# esp-plane-u.net
KiCad netlist of a schematic drawn in Altium Designer
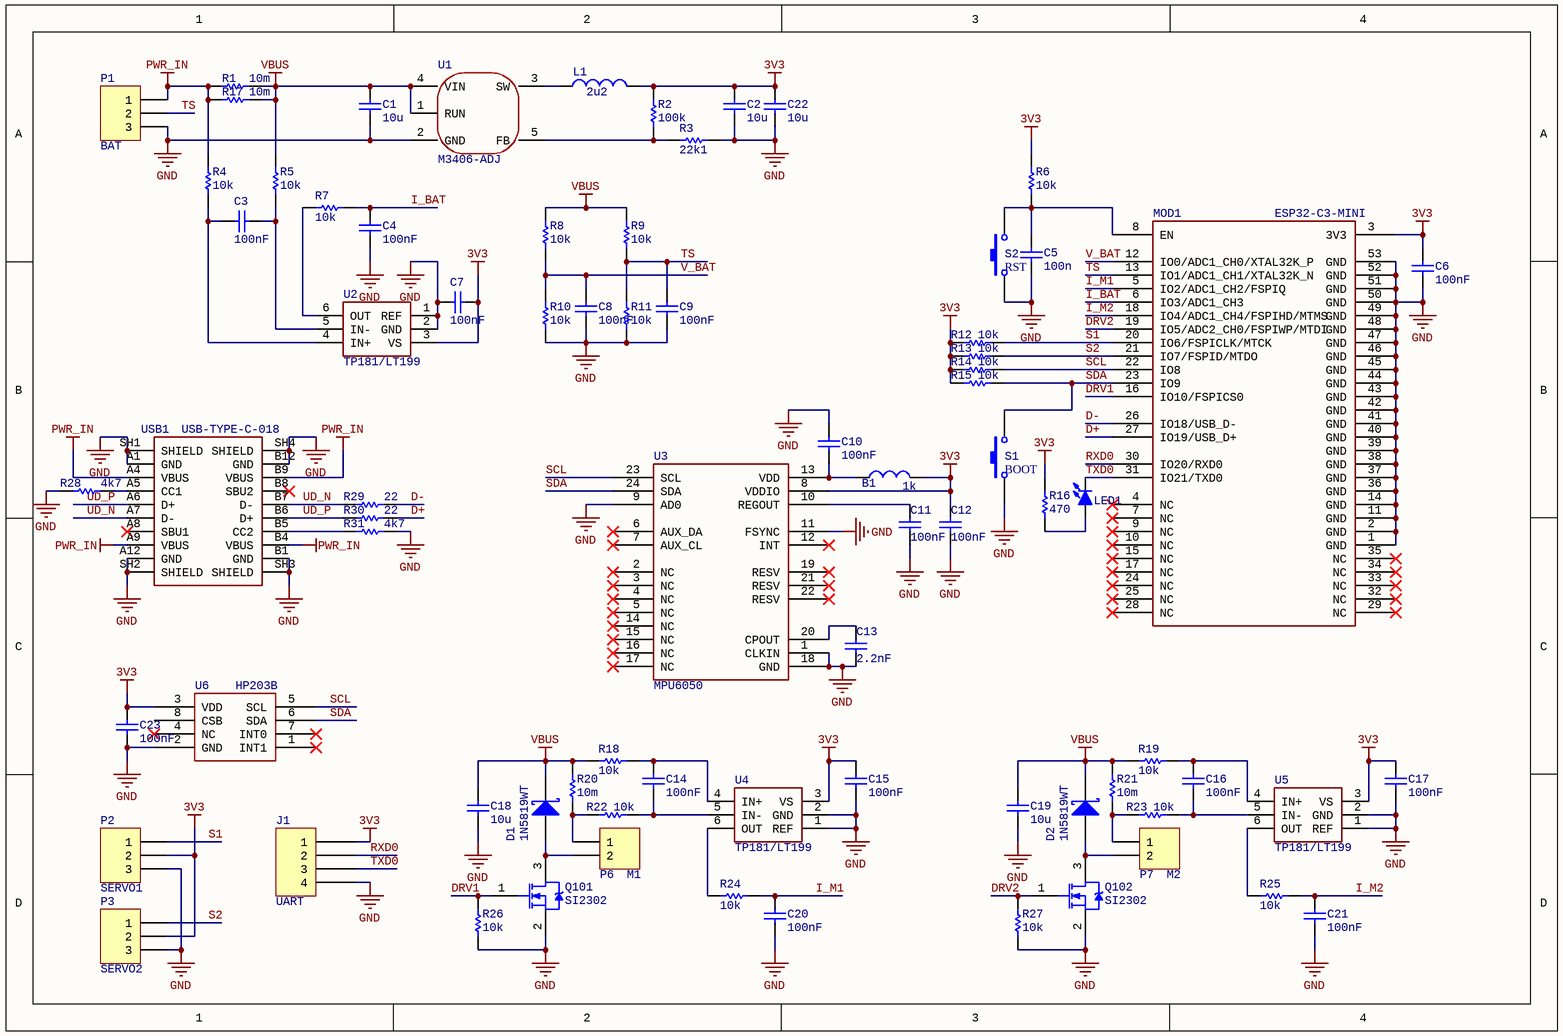
[diagram p0: esp-plane-u.SchDoc]

(export (version "E")
  (design (tool "Eeschema 10.0.6"))
  (components
    (comp (ref "B1")
      (value "1k")
      (footprint "footprints:RESC100X50X35L25N")
      (description "DCR 0.03,2A  0603")
      (fields
        (field (name "MPN") "GZ1005D102CTF")
        (field (name "Comment") "BEAD-470-100MHZ-1A-0603-BLM18PG471SN1")
      )
      (libsource (lib "*") (part "BEAD-470-100MHZ-1A-0603-BLM18PG471SN1"))
    )
    (comp (ref "C1")
      (value "10u")
      (footprint "footprints:CAPC160X80X90L30N")
      (fields (field (name "MPN") "TCC0603X5R106K100CT"))
      (libsource (lib "std_lib") (part "Capacitor"))
    )
    (comp (ref "C2")
      (value "10u")
      (footprint "footprints:CAPC160X80X90L30N")
      (fields (field (name "MPN") "TCC0603X5R106K100CT"))
      (libsource (lib "std_lib") (part "Capacitor"))
    )
    (comp (ref "C3")
      (value "100nF")
      (footprint "footprints:CAPC100X50X55L25N")
      (description "Capacitor")
      (libsource (lib "Miscellaneous Devices") (part "Cap"))
    )
    (comp (ref "C4")
      (value "100nF")
      (footprint "footprints:CAPC100X50X55L25N")
      (description "Capacitor")
      (libsource (lib "Miscellaneous Devices") (part "Cap"))
    )
    (comp (ref "C5")
      (value "100n")
      (footprint "footprints:CAPC100X50X55L25N")
      (fields (field (name "MPN") "TCC0603X5R106K100CT"))
      (libsource (lib "std_lib") (part "Capacitor"))
    )
    (comp (ref "C6")
      (value "100nF")
      (footprint "footprints:CAPC100X50X55L25N")
      (description "Capacitor")
      (libsource (lib "Miscellaneous Devices") (part "Cap"))
    )
    (comp (ref "C7")
      (value "100nF")
      (footprint "footprints:CAPC100X50X55L25N")
      (description "Capacitor")
      (libsource (lib "Miscellaneous Devices") (part "Cap"))
    )
    (comp (ref "C8")
      (value "100nF")
      (footprint "footprints:CAPC100X50X55L25N")
      (description "Capacitor")
      (libsource (lib "Miscellaneous Devices") (part "Cap"))
    )
    (comp (ref "C9")
      (value "100nF")
      (footprint "footprints:CAPC100X50X55L25N")
      (description "Capacitor")
      (libsource (lib "Miscellaneous Devices") (part "Cap"))
    )
    (comp (ref "C10")
      (value "100nF")
      (footprint "footprints:CAPC100X50X55L25N")
      (description "Capacitor (Semiconductor SIM Model)")
      (libsource (lib "Miscellaneous Devices") (part "Cap Semi"))
    )
    (comp (ref "C11")
      (value "100nF")
      (footprint "footprints:CAPC100X50X55L25N")
      (description "Capacitor (Semiconductor SIM Model)")
      (libsource (lib "Miscellaneous Devices") (part "Cap Semi"))
    )
    (comp (ref "C12")
      (value "100nF")
      (footprint "footprints:CAPC100X50X55L25N")
      (description "Capacitor (Semiconductor SIM Model)")
      (libsource (lib "Miscellaneous Devices") (part "Cap Semi"))
    )
    (comp (ref "C13")
      (value "2.2nF")
      (footprint "footprints:CAPC100X50X55L25N")
      (description "Capacitor (Semiconductor SIM Model)")
      (libsource (lib "Miscellaneous Devices") (part "Cap Semi"))
    )
    (comp (ref "C14")
      (value "100nF")
      (footprint "footprints:CAPC100X50X55L25N")
      (description "Capacitor")
      (libsource (lib "Miscellaneous Devices") (part "Cap"))
    )
    (comp (ref "C15")
      (value "100nF")
      (footprint "footprints:CAPC100X50X55L25N")
      (description "Capacitor")
      (libsource (lib "Miscellaneous Devices") (part "Cap"))
    )
    (comp (ref "C16")
      (value "100nF")
      (footprint "footprints:CAPC100X50X55L25N")
      (description "Capacitor")
      (libsource (lib "Miscellaneous Devices") (part "Cap"))
    )
    (comp (ref "C17")
      (value "100nF")
      (footprint "footprints:CAPC100X50X55L25N")
      (description "Capacitor")
      (libsource (lib "Miscellaneous Devices") (part "Cap"))
    )
    (comp (ref "C18")
      (value "10u")
      (footprint "footprints:CAPC160X80X90L30N")
      (description "Capacitor")
      (libsource (lib "Miscellaneous Devices") (part "Cap"))
    )
    (comp (ref "C19")
      (value "10u")
      (footprint "footprints:CAPC160X80X90L30N")
      (description "Capacitor")
      (libsource (lib "Miscellaneous Devices") (part "Cap"))
    )
    (comp (ref "C20")
      (value "100nF")
      (footprint "footprints:CAPC100X50X55L25N")
      (description "Capacitor")
      (libsource (lib "Miscellaneous Devices") (part "Cap"))
    )
    (comp (ref "C21")
      (value "100nF")
      (footprint "footprints:CAPC100X50X55L25N")
      (description "Capacitor")
      (libsource (lib "Miscellaneous Devices") (part "Cap"))
    )
    (comp (ref "C22")
      (value "10u")
      (footprint "footprints:CAPC160X80X90L30N")
      (fields (field (name "MPN") "TCC0603X5R106K100CT"))
      (libsource (lib "std_lib") (part "Capacitor"))
    )
    (comp (ref "C23")
      (value "100nF")
      (footprint "footprints:CAPC100X50X55L25N")
      (description "Capacitor (Semiconductor SIM Model)")
      (libsource (lib "Miscellaneous Devices") (part "Cap Semi"))
    )
    (comp (ref "D1")
      (value "1N5819WT")
      (footprint "footprints:SOD-523")
      (description "Schottky Diode")
      (libsource (lib "Miscellaneous Devices") (part "D Schottky"))
    )
    (comp (ref "D2")
      (value "1N5819WT")
      (footprint "footprints:SOD-523")
      (description "Schottky Diode")
      (libsource (lib "Miscellaneous Devices") (part "D Schottky"))
    )
    (comp (ref "J1")
      (value "UART")
      (footprint "footprints:FPC-SMD_4P-P1.25_DEALON_1.25-4PS")
      (libsource (lib "SCH - CONNECTORS - 4 PIN") (part "4 Pin"))
    )
    (comp (ref "L1")
      (value "2u2")
      (footprint "footprints:INDC200X160X105L60N")
      (fields (field (name "MPN") "SFE201610-2R2M") (field (name "Comment") "Inductor"))
      (libsource (lib "std_lib") (part "Inductor"))
    )
    (comp (ref "LED1")
      (value "蓝灯 正贴")
      (footprint "footprints:LEDC100X50X45L25N")
      (description "贴片LED")
      (libsource (lib "mcontroller") (part "LED-SMD"))
    )
    (comp (ref "MOD1")
      (value "ESP32-C3-MINI")
      (footprint "footprints:ESP32-C3-MINI-1U")
      (libsource (lib "Sch") (part "ESP32-C3-MINI"))
    )
    (comp (ref "P1")
      (value "BAT")
      (footprint "footprints:BC-1-319")
      (description "Header, 3-Pin")
      (libsource (lib "Miscellaneous Connectors") (part "Header 3"))
    )
    (comp (ref "P2")
      (value "SERVO1")
      (footprint "footprints:FPC-SMD_3P-P1.25_DEALON_1.25-3PS-1")
      (description "Header, 3-Pin")
      (libsource (lib "Miscellaneous Connectors") (part "Header 3"))
    )
    (comp (ref "P3")
      (value "SERVO2")
      (footprint "footprints:FPC-SMD_3P-P1.25_DEALON_1.25-3PS-1")
      (description "Header, 3-Pin")
      (libsource (lib "Miscellaneous Connectors") (part "Header 3"))
    )
    (comp (ref "P6")
      (value "M1")
      (footprint "footprints:CONN-SMD_2P-P1.25_DEALON_1.25-2PS")
      (description "Header, 2-Pin")
      (libsource (lib "Miscellaneous Connectors") (part "Header 2"))
    )
    (comp (ref "P7")
      (value "M2")
      (footprint "footprints:CONN-SMD_2P-P1.25_DEALON_1.25-2PS")
      (description "Header, 2-Pin")
      (libsource (lib "Miscellaneous Connectors") (part "Header 2"))
    )
    (comp (ref "Q101")
      (value "SI2302")
      (footprint "footprints:SOT23-3P95_237X111L52X43N")
      (description "N-Channel Power MOSFET")
      (libsource (lib "Sch") (part "NMOS-2"))
    )
    (comp (ref "Q102")
      (value "SI2302")
      (footprint "footprints:SOT23-3P95_237X111L52X43N")
      (description "N-Channel Power MOSFET")
      (libsource (lib "Sch") (part "NMOS-2"))
    )
    (comp (ref "R1")
      (value "10m")
      (footprint "footprints:RES 0603/1608")
      (description "Resistor")
      (libsource (lib "Miscellaneous Devices") (part "Res1"))
    )
    (comp (ref "R2")
      (value "100k")
      (footprint "footprints:RESC100X50X35L25N")
      (fields (field (name "MPN") "RTT021003FTH"))
      (libsource (lib "std_lib") (part "Resistor"))
    )
    (comp (ref "R3")
      (value "22k1")
      (footprint "footprints:RESC100X50X35L25N")
      (fields (field (name "MPN") "RTT022212FTH"))
      (libsource (lib "std_lib") (part "Resistor"))
    )
    (comp (ref "R4")
      (value "10k")
      (footprint "footprints:RESC100X50X35L25N")
      (description "Resistor")
      (libsource (lib "Miscellaneous Devices") (part "Res1"))
    )
    (comp (ref "R5")
      (value "10k")
      (footprint "footprints:RESC100X50X35L25N")
      (description "Resistor")
      (libsource (lib "Miscellaneous Devices") (part "Res1"))
    )
    (comp (ref "R6")
      (value "10k")
      (footprint "footprints:RESC100X50X35L25N")
      (fields (field (name "MPN") "RTT022212FTH"))
      (libsource (lib "std_lib") (part "Resistor"))
    )
    (comp (ref "R7")
      (value "10k")
      (footprint "footprints:RESC100X50X35L25N")
      (description "Resistor")
      (libsource (lib "Miscellaneous Devices") (part "Res1"))
    )
    (comp (ref "R8")
      (value "10k")
      (footprint "footprints:RESC100X50X35L25N")
      (description "Resistor")
      (libsource (lib "Miscellaneous Devices") (part "Res1"))
    )
    (comp (ref "R9")
      (value "10k")
      (footprint "footprints:RESC100X50X35L25N")
      (description "Resistor")
      (libsource (lib "Miscellaneous Devices") (part "Res1"))
    )
    (comp (ref "R10")
      (value "10k")
      (footprint "footprints:RESC100X50X35L25N")
      (description "Resistor")
      (libsource (lib "Miscellaneous Devices") (part "Res1"))
    )
    (comp (ref "R11")
      (value "10k")
      (footprint "footprints:RESC100X50X35L25N")
      (description "Resistor")
      (libsource (lib "Miscellaneous Devices") (part "Res1"))
    )
    (comp (ref "R12")
      (value "10k")
      (footprint "footprints:RESC100X50X35L25N")
      (fields (field (name "MPN") "RTT02471JTH"))
      (libsource (lib "std_lib") (part "Resistor"))
    )
    (comp (ref "R13")
      (value "10k")
      (footprint "footprints:RESC100X50X35L25N")
      (fields (field (name "MPN") "RTT02471JTH"))
      (libsource (lib "std_lib") (part "Resistor"))
    )
    (comp (ref "R14")
      (value "10k")
      (footprint "footprints:RESC100X50X35L25N")
      (fields (field (name "MPN") "RTT02471JTH"))
      (libsource (lib "std_lib") (part "Resistor"))
    )
    (comp (ref "R15")
      (value "10k")
      (footprint "footprints:RESC100X50X35L25N")
      (fields (field (name "MPN") "RTT02471JTH"))
      (libsource (lib "std_lib") (part "Resistor"))
    )
    (comp (ref "R16")
      (value "470")
      (footprint "footprints:RESC100X50X35L25N")
      (fields (field (name "MPN") "RTT02471JTH"))
      (libsource (lib "std_lib") (part "Resistor"))
    )
    (comp (ref "R17")
      (value "10m")
      (footprint "footprints:RES 0603/1608")
      (description "Resistor")
      (libsource (lib "Miscellaneous Devices") (part "Res1"))
    )
    (comp (ref "R18")
      (value "10k")
      (footprint "footprints:RESC100X50X35L25N")
      (description "Resistor")
      (libsource (lib "Miscellaneous Devices") (part "Res1"))
    )
    (comp (ref "R19")
      (value "10k")
      (footprint "footprints:RESC100X50X35L25N")
      (description "Resistor")
      (libsource (lib "Miscellaneous Devices") (part "Res1"))
    )
    (comp (ref "R20")
      (value "10m")
      (footprint "footprints:RES 0603/1608")
      (description "Resistor")
      (libsource (lib "Miscellaneous Devices") (part "Res1"))
    )
    (comp (ref "R21")
      (value "10m")
      (footprint "footprints:RES 0603/1608")
      (description "Resistor")
      (libsource (lib "Miscellaneous Devices") (part "Res1"))
    )
    (comp (ref "R22")
      (value "10k")
      (footprint "footprints:RESC100X50X35L25N")
      (description "Resistor")
      (libsource (lib "Miscellaneous Devices") (part "Res1"))
    )
    (comp (ref "R23")
      (value "10k")
      (footprint "footprints:RESC100X50X35L25N")
      (description "Resistor")
      (libsource (lib "Miscellaneous Devices") (part "Res1"))
    )
    (comp (ref "R24")
      (value "10k")
      (footprint "footprints:RESC100X50X35L25N")
      (description "Resistor")
      (libsource (lib "Miscellaneous Devices") (part "Res1"))
    )
    (comp (ref "R25")
      (value "10k")
      (footprint "footprints:RESC100X50X35L25N")
      (description "Resistor")
      (libsource (lib "Miscellaneous Devices") (part "Res1"))
    )
    (comp (ref "R26")
      (value "10k")
      (footprint "footprints:RESC100X50X35L25N")
      (description "Resistor")
      (libsource (lib "Miscellaneous Devices") (part "Res1"))
    )
    (comp (ref "R27")
      (value "10k")
      (footprint "footprints:RESC100X50X35L25N")
      (description "Resistor")
      (libsource (lib "Miscellaneous Devices") (part "Res1"))
    )
    (comp (ref "R28")
      (value "4k7")
      (footprint "footprints:RESC100X50X35L25N")
      (fields (field (name "MPN") "RTT02472JTH"))
      (libsource (lib "std_lib") (part "Resistor"))
    )
    (comp (ref "R29")
      (value "22")
      (footprint "footprints:RESC100X50X35L25N")
      (fields (field (name "MPN") "RTT02472JTH"))
      (libsource (lib "std_lib") (part "Resistor"))
    )
    (comp (ref "R30")
      (value "22")
      (footprint "footprints:RESC100X50X35L25N")
      (fields (field (name "MPN") "RTT02472JTH"))
      (libsource (lib "std_lib") (part "Resistor"))
    )
    (comp (ref "R31")
      (value "4k7")
      (footprint "footprints:RESC100X50X35L25N")
      (fields (field (name "MPN") "RTT02472JTH"))
      (libsource (lib "std_lib") (part "Resistor"))
    )
    (comp (ref "S1")
      (value "BOOT")
      (footprint "footprints:KEY-3*4")
      (description "Switch")
      (libsource (lib "Miscellaneous Devices") (part "SW-PB"))
    )
    (comp (ref "S2")
      (value "RST")
      (footprint "footprints:KEY-3*4")
      (description "Switch")
      (libsource (lib "Miscellaneous Devices") (part "SW-PB"))
    )
    (comp (ref "U1")
      (value "M3406-ADJ")
      (footprint "footprints:SOT23-5P95_280X110L37X40N")
      (description "Vin=2V~6V,800mA,DCDC")
      (libsource (lib "Sch") (part "M3406-ADJ"))
    )
    (comp (ref "U2")
      (value "TP181/LT199")
      (footprint "footprints:SC-70-6_L2.0-W1.3-P0.65-LS2.2-BL")
      (libsource (lib "") (part "LT199_SC70-6L_1"))
    )
    (comp (ref "U3")
      (value "MPU6050")
      (footprint "footprints:IMU-3000")
      (libsource (lib "Sch") (part "MPU6050"))
    )
    (comp (ref "U4")
      (value "TP181/LT199")
      (footprint "footprints:SC-70-6_L2.0-W1.3-P0.65-LS2.2-BL")
      (libsource (lib "Sch") (part "LT199_SC70-6L"))
    )
    (comp (ref "U5")
      (value "TP181/LT199")
      (footprint "footprints:SC-70-6_L2.0-W1.3-P0.65-LS2.2-BL")
      (libsource (lib "Sch") (part "LT199_SC70-6L"))
    )
    (comp (ref "U6")
      (value "HP203B")
      (footprint "footprints:HP203B")
      (libsource (lib "mcontroller") (part "HP203B"))
    )
    (comp (ref "USB1")
      (value "USB-TYPE-C-018")
      (footprint "footprints:USB-TYPE-C-018")
      (libsource (lib "Sch") (part "USB-TYPE-C-018"))
    )
  )
  (nets
    (net (code "1") (name "/D+") (class "Default")
      (node (ref "MOD1") (pin "27") (pinfunction "IO19/USB_D+_27") (pintype "passive"))
      (node (ref "R30") (pin "1") (pinfunction "1_1") (pintype "passive"))
    )
    (net (code "2") (name "/D-") (class "Default")
      (node (ref "MOD1") (pin "26") (pinfunction "IO18/USB_D-_26") (pintype "passive"))
      (node (ref "R29") (pin "1") (pinfunction "1_1") (pintype "passive"))
    )
    (net (code "3") (name "/DRV1") (class "Default")
      (node (ref "MOD1") (pin "16") (pinfunction "IO10/FSPICS0_16") (pintype "passive"))
      (node (ref "Q101") (pin "1") (pinfunction "G_1") (pintype "passive"))
      (node (ref "R26") (pin "2") (pinfunction "2_2") (pintype "passive"))
    )
    (net (code "4") (name "/DRV2") (class "Default")
      (node (ref "MOD1") (pin "19") (pinfunction "IO5/ADC2_CH0/FSPIWP/MTDI_19") (pintype "passive"))
      (node (ref "Q102") (pin "1") (pinfunction "G_1") (pintype "passive"))
      (node (ref "R27") (pin "2") (pinfunction "2_2") (pintype "passive"))
    )
    (net (code "5") (name "/I_BAT") (class "Default")
      (node (ref "C4") (pin "2") (pinfunction "2_2") (pintype "passive"))
      (node (ref "MOD1") (pin "6") (pinfunction "IO3/ADC1_CH3_6") (pintype "passive"))
      (node (ref "R7") (pin "2") (pinfunction "2_2") (pintype "passive"))
    )
    (net (code "6") (name "/I_M1") (class "Default")
      (node (ref "C20") (pin "2") (pinfunction "2_2") (pintype "passive"))
      (node (ref "MOD1") (pin "5") (pinfunction "IO2/ADC1_CH2/FSPIQ_5") (pintype "passive"))
      (node (ref "R24") (pin "2") (pinfunction "2_2") (pintype "passive"))
    )
    (net (code "7") (name "/I_M2") (class "Default")
      (node (ref "C21") (pin "2") (pinfunction "2_2") (pintype "passive"))
      (node (ref "MOD1") (pin "18") (pinfunction "IO4/ADC1_CH4/FSPIHD/MTMS_18") (pintype "passive"))
      (node (ref "R25") (pin "2") (pinfunction "2_2") (pintype "passive"))
    )
    (net (code "8") (name "/RXD0") (class "Default")
      (node (ref "J1") (pin "2") (pinfunction "2_2") (pintype "passive"))
      (node (ref "MOD1") (pin "30") (pinfunction "IO20/RXD0_30") (pintype "passive"))
    )
    (net (code "9") (name "/S1") (class "Default")
      (node (ref "MOD1") (pin "20") (pinfunction "IO6/FSPICLK/MTCK_20") (pintype "passive"))
      (node (ref "P2") (pin "1") (pinfunction "1_1") (pintype "passive"))
      (node (ref "R12") (pin "2") (pinfunction "2_2") (pintype "passive"))
    )
    (net (code "10") (name "/S2") (class "Default")
      (node (ref "MOD1") (pin "21") (pinfunction "IO7/FSPID/MTDO_21") (pintype "passive"))
      (node (ref "P3") (pin "1") (pinfunction "1_1") (pintype "passive"))
      (node (ref "R13") (pin "2") (pinfunction "2_2") (pintype "passive"))
    )
    (net (code "11") (name "/SCL") (class "Default")
      (node (ref "MOD1") (pin "22") (pinfunction "IO8_22") (pintype "passive"))
      (node (ref "R14") (pin "2") (pinfunction "2_2") (pintype "passive"))
      (node (ref "U3") (pin "23") (pinfunction "SCL_23") (pintype "passive"))
      (node (ref "U6") (pin "5") (pinfunction "SCL_5") (pintype "passive"))
    )
    (net (code "12") (name "/SDA") (class "Default")
      (node (ref "MOD1") (pin "23") (pinfunction "IO9_23") (pintype "passive"))
      (node (ref "R15") (pin "2") (pinfunction "2_2") (pintype "passive"))
      (node (ref "S1") (pin "1") (pinfunction "1_1") (pintype "passive"))
      (node (ref "U3") (pin "24") (pinfunction "SDA_24") (pintype "passive"))
      (node (ref "U6") (pin "6") (pinfunction "SDA_6") (pintype "passive"))
    )
    (net (code "13") (name "/TS") (class "Default")
      (node (ref "C9") (pin "1") (pinfunction "1_1") (pintype "passive"))
      (node (ref "MOD1") (pin "13") (pinfunction "IO1/ADC1_CH1/XTAL32K_N_13") (pintype "passive"))
      (node (ref "P1") (pin "2") (pinfunction "2_2") (pintype "passive"))
      (node (ref "R11") (pin "2") (pinfunction "2_2") (pintype "passive"))
      (node (ref "R9") (pin "1") (pinfunction "1_1") (pintype "passive"))
    )
    (net (code "14") (name "/TXD0") (class "Default")
      (node (ref "J1") (pin "3") (pinfunction "3_3") (pintype "passive"))
      (node (ref "LED1") (pin "C") (pinfunction "K_C") (pintype "passive"))
      (node (ref "MOD1") (pin "31") (pinfunction "IO21/TXD0_31") (pintype "passive"))
    )
    (net (code "15") (name "/UD_N") (class "Default")
      (node (ref "R29") (pin "2") (pinfunction "2_2") (pintype "passive"))
      (node (ref "USB1") (pin "A7") (pinfunction "D-_A7") (pintype "passive"))
      (node (ref "USB1") (pin "B7") (pinfunction "D-_B7") (pintype "passive"))
    )
    (net (code "16") (name "/UD_P") (class "Default")
      (node (ref "R30") (pin "2") (pinfunction "2_2") (pintype "passive"))
      (node (ref "USB1") (pin "A6") (pinfunction "D+_A6") (pintype "passive"))
      (node (ref "USB1") (pin "B6") (pinfunction "D+_B6") (pintype "passive"))
    )
    (net (code "17") (name "/V_BAT") (class "Default")
      (node (ref "C8") (pin "1") (pinfunction "1_1") (pintype "passive"))
      (node (ref "MOD1") (pin "12") (pinfunction "IO0/ADC1_CH0/XTAL32K_P_12") (pintype "passive"))
      (node (ref "R10") (pin "2") (pinfunction "2_2") (pintype "passive"))
      (node (ref "R8") (pin "1") (pinfunction "1_1") (pintype "passive"))
    )
    (net (code "18") (name "3V3") (class "Default")
      (node (ref "B1") (pin "2") (pinfunction "2_2") (pintype "passive"))
      (node (ref "C12") (pin "1") (pinfunction "1_1") (pintype "passive"))
      (node (ref "C15") (pin "2") (pinfunction "2_2") (pintype "passive"))
      (node (ref "C17") (pin "2") (pinfunction "2_2") (pintype "passive"))
      (node (ref "C2") (pin "2") (pinfunction "2_2") (pintype "passive"))
      (node (ref "C22") (pin "2") (pinfunction "2_2") (pintype "passive"))
      (node (ref "C23") (pin "1") (pinfunction "1_1") (pintype "passive"))
      (node (ref "C6") (pin "2") (pinfunction "2_2") (pintype "passive"))
      (node (ref "C7") (pin "1") (pinfunction "1_1") (pintype "passive"))
      (node (ref "J1") (pin "1") (pinfunction "1_1") (pintype "passive"))
      (node (ref "L1") (pin "2") (pinfunction "2_2") (pintype "passive"))
      (node (ref "MOD1") (pin "3") (pinfunction "3V3_3") (pintype "passive"))
      (node (ref "P2") (pin "2") (pinfunction "2_2") (pintype "passive"))
      (node (ref "P3") (pin "2") (pinfunction "2_2") (pintype "passive"))
      (node (ref "R12") (pin "1") (pinfunction "1_1") (pintype "passive"))
      (node (ref "R13") (pin "1") (pinfunction "1_1") (pintype "passive"))
      (node (ref "R14") (pin "1") (pinfunction "1_1") (pintype "passive"))
      (node (ref "R15") (pin "1") (pinfunction "1_1") (pintype "passive"))
      (node (ref "R16") (pin "2") (pinfunction "2_2") (pintype "passive"))
      (node (ref "R2") (pin "2") (pinfunction "2_2") (pintype "passive"))
      (node (ref "R6") (pin "2") (pinfunction "2_2") (pintype "passive"))
      (node (ref "U2") (pin "3") (pinfunction "VS_3") (pintype "passive"))
      (node (ref "U3") (pin "8") (pinfunction "VDDIO_8") (pintype "passive"))
      (node (ref "U4") (pin "3") (pinfunction "VS_3") (pintype "passive"))
      (node (ref "U5") (pin "3") (pinfunction "VS_3") (pintype "passive"))
      (node (ref "U6") (pin "3") (pinfunction "VDD_3") (pintype "passive"))
    )
    (net (code "19") (name "GND") (class "Default")
      (node (ref "C1") (pin "1") (pinfunction "1_1") (pintype "passive"))
      (node (ref "C10") (pin "1") (pinfunction "1_1") (pintype "passive"))
      (node (ref "C11") (pin "1") (pinfunction "1_1") (pintype "passive"))
      (node (ref "C12") (pin "2") (pinfunction "2_2") (pintype "passive"))
      (node (ref "C13") (pin "1") (pinfunction "1_1") (pintype "passive"))
      (node (ref "C15") (pin "1") (pinfunction "1_1") (pintype "passive"))
      (node (ref "C17") (pin "1") (pinfunction "1_1") (pintype "passive"))
      (node (ref "C18") (pin "1") (pinfunction "1_1") (pintype "passive"))
      (node (ref "C19") (pin "1") (pinfunction "1_1") (pintype "passive"))
      (node (ref "C2") (pin "1") (pinfunction "1_1") (pintype "passive"))
      (node (ref "C20") (pin "1") (pinfunction "1_1") (pintype "passive"))
      (node (ref "C21") (pin "1") (pinfunction "1_1") (pintype "passive"))
      (node (ref "C22") (pin "1") (pinfunction "1_1") (pintype "passive"))
      (node (ref "C23") (pin "2") (pinfunction "2_2") (pintype "passive"))
      (node (ref "C4") (pin "1") (pinfunction "1_1") (pintype "passive"))
      (node (ref "C5") (pin "1") (pinfunction "1_1") (pintype "passive"))
      (node (ref "C6") (pin "1") (pinfunction "1_1") (pintype "passive"))
      (node (ref "C7") (pin "2") (pinfunction "2_2") (pintype "passive"))
      (node (ref "C8") (pin "2") (pinfunction "2_2") (pintype "passive"))
      (node (ref "C9") (pin "2") (pinfunction "2_2") (pintype "passive"))
      (node (ref "J1") (pin "4") (pinfunction "4_4") (pintype "passive"))
      (node (ref "MOD1") (pin "1") (pinfunction "GND_1") (pintype "passive"))
      (node (ref "MOD1") (pin "11") (pinfunction "GND_11") (pintype "passive"))
      (node (ref "MOD1") (pin "14") (pinfunction "GND_14") (pintype "passive"))
      (node (ref "MOD1") (pin "2") (pinfunction "GND_2") (pintype "passive"))
      (node (ref "MOD1") (pin "36") (pinfunction "GND_36") (pintype "passive"))
      (node (ref "MOD1") (pin "37") (pinfunction "GND_37") (pintype "passive"))
      (node (ref "MOD1") (pin "38") (pinfunction "GND_38") (pintype "passive"))
      (node (ref "MOD1") (pin "39") (pinfunction "GND_39") (pintype "passive"))
      (node (ref "MOD1") (pin "40") (pinfunction "GND_40") (pintype "passive"))
      (node (ref "MOD1") (pin "41") (pinfunction "GND_41") (pintype "passive"))
      (node (ref "MOD1") (pin "42") (pinfunction "GND_42") (pintype "passive"))
      (node (ref "MOD1") (pin "43") (pinfunction "GND_43") (pintype "passive"))
      (node (ref "MOD1") (pin "44") (pinfunction "GND_44") (pintype "passive"))
      (node (ref "MOD1") (pin "45") (pinfunction "GND_45") (pintype "passive"))
      (node (ref "MOD1") (pin "46") (pinfunction "GND_46") (pintype "passive"))
      (node (ref "MOD1") (pin "47") (pinfunction "GND_47") (pintype "passive"))
      (node (ref "MOD1") (pin "48") (pinfunction "GND_48") (pintype "passive"))
      (node (ref "MOD1") (pin "49") (pinfunction "GND_49") (pintype "passive"))
      (node (ref "MOD1") (pin "50") (pinfunction "GND_50") (pintype "passive"))
      (node (ref "MOD1") (pin "51") (pinfunction "GND_51") (pintype "passive"))
      (node (ref "MOD1") (pin "52") (pinfunction "GND_52") (pintype "passive"))
      (node (ref "MOD1") (pin "53") (pinfunction "GND_53") (pintype "passive"))
      (node (ref "P1") (pin "3") (pinfunction "3_3") (pintype "passive"))
      (node (ref "P2") (pin "3") (pinfunction "3_3") (pintype "passive"))
      (node (ref "P3") (pin "3") (pinfunction "3_3") (pintype "passive"))
      (node (ref "Q101") (pin "2") (pinfunction "S_2") (pintype "passive"))
      (node (ref "Q102") (pin "2") (pinfunction "S_2") (pintype "passive"))
      (node (ref "R10") (pin "1") (pinfunction "1_1") (pintype "passive"))
      (node (ref "R11") (pin "1") (pinfunction "1_1") (pintype "passive"))
      (node (ref "R26") (pin "1") (pinfunction "1_1") (pintype "passive"))
      (node (ref "R27") (pin "1") (pinfunction "1_1") (pintype "passive"))
      (node (ref "R28") (pin "2") (pinfunction "2_2") (pintype "passive"))
      (node (ref "R3") (pin "1") (pinfunction "1_1") (pintype "passive"))
      (node (ref "R31") (pin "1") (pinfunction "1_1") (pintype "passive"))
      (node (ref "S1") (pin "2") (pinfunction "2_2") (pintype "passive"))
      (node (ref "S2") (pin "2") (pinfunction "2_2") (pintype "passive"))
      (node (ref "U1") (pin "2") (pinfunction "GND_2") (pintype "passive"))
      (node (ref "U2") (pin "1") (pinfunction "REF_1") (pintype "passive"))
      (node (ref "U2") (pin "2") (pinfunction "GND_2") (pintype "passive"))
      (node (ref "U3") (pin "1") (pinfunction "CLKIN_1") (pintype "passive"))
      (node (ref "U3") (pin "11") (pinfunction "FSYNC_11") (pintype "passive"))
      (node (ref "U3") (pin "18") (pinfunction "GND_18") (pintype "passive"))
      (node (ref "U3") (pin "9") (pinfunction "AD0_9") (pintype "passive"))
      (node (ref "U4") (pin "1") (pinfunction "REF_1") (pintype "passive"))
      (node (ref "U4") (pin "2") (pinfunction "GND_2") (pintype "passive"))
      (node (ref "U5") (pin "1") (pinfunction "REF_1") (pintype "passive"))
      (node (ref "U5") (pin "2") (pinfunction "GND_2") (pintype "passive"))
      (node (ref "U6") (pin "2") (pinfunction "GND_2") (pintype "passive"))
      (node (ref "USB1") (pin "A1") (pinfunction "GND_A1") (pintype "passive"))
      (node (ref "USB1") (pin "A12") (pinfunction "GND_A12") (pintype "passive"))
      (node (ref "USB1") (pin "B1") (pinfunction "GND_B1") (pintype "passive"))
      (node (ref "USB1") (pin "B12") (pinfunction "GND_B12") (pintype "passive"))
      (node (ref "USB1") (pin "SH1") (pinfunction "SHIELD_SH1") (pintype "passive"))
      (node (ref "USB1") (pin "SH2") (pinfunction "SHIELD_SH2") (pintype "passive"))
      (node (ref "USB1") (pin "SH3") (pinfunction "SHIELD_SH3") (pintype "passive"))
      (node (ref "USB1") (pin "SH4") (pinfunction "SHIELD_SH4") (pintype "passive"))
    )
    (net (code "20") (name "Net-(D1-A)") (class "Default")
      (node (ref "D1") (pin "1") (pinfunction "A_1") (pintype "passive"))
      (node (ref "P6") (pin "2") (pinfunction "2_2") (pintype "passive"))
      (node (ref "Q101") (pin "3") (pinfunction "D_3") (pintype "passive"))
    )
    (net (code "21") (name "Net-(D2-A)") (class "Default")
      (node (ref "D2") (pin "1") (pinfunction "A_1") (pintype "passive"))
      (node (ref "P7") (pin "2") (pinfunction "2_2") (pintype "passive"))
      (node (ref "Q102") (pin "3") (pinfunction "D_3") (pintype "passive"))
    )
    (net (code "22") (name "Net-(LED1-PadA)") (class "Default")
      (node (ref "LED1") (pin "A") (pinfunction "A_A") (pintype "passive"))
      (node (ref "R16") (pin "1") (pinfunction "1_1") (pintype "passive"))
    )
    (net (code "23") (name "Net-(MOD1-EN)") (class "Default")
      (node (ref "C5") (pin "2") (pinfunction "2_2") (pintype "passive"))
      (node (ref "MOD1") (pin "8") (pinfunction "EN_8") (pintype "passive"))
      (node (ref "R6") (pin "1") (pinfunction "1_1") (pintype "passive"))
      (node (ref "S2") (pin "1") (pinfunction "1_1") (pintype "passive"))
    )
    (net (code "24") (name "Net-(P6-Pad1)") (class "Default")
      (node (ref "P6") (pin "1") (pinfunction "1_1") (pintype "passive"))
      (node (ref "R20") (pin "1") (pinfunction "1_1") (pintype "passive"))
      (node (ref "R22") (pin "1") (pinfunction "1_1") (pintype "passive"))
    )
    (net (code "25") (name "Net-(P7-Pad1)") (class "Default")
      (node (ref "P7") (pin "1") (pinfunction "1_1") (pintype "passive"))
      (node (ref "R21") (pin "1") (pinfunction "1_1") (pintype "passive"))
      (node (ref "R23") (pin "1") (pinfunction "1_1") (pintype "passive"))
    )
    (net (code "26") (name "Net-(U1-FB)") (class "Default")
      (node (ref "R2") (pin "1") (pinfunction "1_1") (pintype "passive"))
      (node (ref "R3") (pin "2") (pinfunction "2_2") (pintype "passive"))
      (node (ref "U1") (pin "5") (pinfunction "FB_5") (pintype "passive"))
    )
    (net (code "27") (name "Net-(U1-SW)") (class "Default")
      (node (ref "L1") (pin "1") (pinfunction "1_1") (pintype "passive"))
      (node (ref "U1") (pin "3") (pinfunction "SW_3") (pintype "passive"))
    )
    (net (code "28") (name "Net-(U2-IN+)") (class "Default")
      (node (ref "C3") (pin "1") (pinfunction "1_1") (pintype "passive"))
      (node (ref "R4") (pin "2") (pinfunction "2_2") (pintype "passive"))
      (node (ref "U2") (pin "4") (pinfunction "IN+_4") (pintype "passive"))
    )
    (net (code "29") (name "Net-(U2-IN-)") (class "Default")
      (node (ref "C3") (pin "2") (pinfunction "2_2") (pintype "passive"))
      (node (ref "R5") (pin "2") (pinfunction "2_2") (pintype "passive"))
      (node (ref "U2") (pin "5") (pinfunction "IN-_5") (pintype "passive"))
    )
    (net (code "30") (name "Net-(U2-OUT)") (class "Default")
      (node (ref "R7") (pin "1") (pinfunction "1_1") (pintype "passive"))
      (node (ref "U2") (pin "6") (pinfunction "OUT_6") (pintype "passive"))
    )
    (net (code "31") (name "Net-(U3-CPOUT)") (class "Default")
      (node (ref "C13") (pin "2") (pinfunction "2_2") (pintype "passive"))
      (node (ref "U3") (pin "20") (pinfunction "CPOUT_20") (pintype "passive"))
    )
    (net (code "32") (name "Net-(U3-REGOUT)") (class "Default")
      (node (ref "C11") (pin "2") (pinfunction "2_2") (pintype "passive"))
      (node (ref "U3") (pin "10") (pinfunction "REGOUT_10") (pintype "passive"))
    )
    (net (code "33") (name "Net-(U3-VDD)") (class "Default")
      (node (ref "B1") (pin "1") (pinfunction "1_1") (pintype "passive"))
      (node (ref "C10") (pin "2") (pinfunction "2_2") (pintype "passive"))
      (node (ref "U3") (pin "13") (pinfunction "VDD_13") (pintype "passive"))
    )
    (net (code "34") (name "Net-(U4-IN+)") (class "Default")
      (node (ref "C14") (pin "2") (pinfunction "2_2") (pintype "passive"))
      (node (ref "R18") (pin "2") (pinfunction "2_2") (pintype "passive"))
      (node (ref "U4") (pin "4") (pinfunction "IN+_4") (pintype "passive"))
    )
    (net (code "35") (name "Net-(U4-IN-)") (class "Default")
      (node (ref "C14") (pin "1") (pinfunction "1_1") (pintype "passive"))
      (node (ref "R22") (pin "2") (pinfunction "2_2") (pintype "passive"))
      (node (ref "U4") (pin "5") (pinfunction "IN-_5") (pintype "passive"))
    )
    (net (code "36") (name "Net-(U4-OUT)") (class "Default")
      (node (ref "R24") (pin "1") (pinfunction "1_1") (pintype "passive"))
      (node (ref "U4") (pin "6") (pinfunction "OUT_6") (pintype "passive"))
    )
    (net (code "37") (name "Net-(U5-IN+)") (class "Default")
      (node (ref "C16") (pin "2") (pinfunction "2_2") (pintype "passive"))
      (node (ref "R19") (pin "2") (pinfunction "2_2") (pintype "passive"))
      (node (ref "U5") (pin "4") (pinfunction "IN+_4") (pintype "passive"))
    )
    (net (code "38") (name "Net-(U5-IN-)") (class "Default")
      (node (ref "C16") (pin "1") (pinfunction "1_1") (pintype "passive"))
      (node (ref "R23") (pin "2") (pinfunction "2_2") (pintype "passive"))
      (node (ref "U5") (pin "5") (pinfunction "IN-_5") (pintype "passive"))
    )
    (net (code "39") (name "Net-(U5-OUT)") (class "Default")
      (node (ref "R25") (pin "1") (pinfunction "1_1") (pintype "passive"))
      (node (ref "U5") (pin "6") (pinfunction "OUT_6") (pintype "passive"))
    )
    (net (code "40") (name "Net-(USB1-CC1)") (class "Default")
      (node (ref "R28") (pin "1") (pinfunction "1_1") (pintype "passive"))
      (node (ref "USB1") (pin "A5") (pinfunction "CC1_A5") (pintype "passive"))
    )
    (net (code "41") (name "Net-(USB1-CC2)") (class "Default")
      (node (ref "R31") (pin "2") (pinfunction "2_2") (pintype "passive"))
      (node (ref "USB1") (pin "B5") (pinfunction "CC2_B5") (pintype "passive"))
    )
    (net (code "42") (name "PWR_IN") (class "Default")
      (node (ref "P1") (pin "1") (pinfunction "1_1") (pintype "passive"))
      (node (ref "R1") (pin "2") (pinfunction "2_2") (pintype "passive"))
      (node (ref "R17") (pin "2") (pinfunction "2_2") (pintype "passive"))
      (node (ref "R4") (pin "1") (pinfunction "1_1") (pintype "passive"))
      (node (ref "USB1") (pin "A4") (pinfunction "VBUS_A4") (pintype "passive"))
      (node (ref "USB1") (pin "A9") (pinfunction "VBUS_A9") (pintype "passive"))
      (node (ref "USB1") (pin "B4") (pinfunction "VBUS_B4") (pintype "passive"))
      (node (ref "USB1") (pin "B9") (pinfunction "VBUS_B9") (pintype "passive"))
    )
    (net (code "43") (name "VBUS") (class "Default")
      (node (ref "C1") (pin "2") (pinfunction "2_2") (pintype "passive"))
      (node (ref "C18") (pin "2") (pinfunction "2_2") (pintype "passive"))
      (node (ref "C19") (pin "2") (pinfunction "2_2") (pintype "passive"))
      (node (ref "D1") (pin "2") (pinfunction "K_2") (pintype "passive"))
      (node (ref "D2") (pin "2") (pinfunction "K_2") (pintype "passive"))
      (node (ref "R1") (pin "1") (pinfunction "1_1") (pintype "passive"))
      (node (ref "R17") (pin "1") (pinfunction "1_1") (pintype "passive"))
      (node (ref "R18") (pin "1") (pinfunction "1_1") (pintype "passive"))
      (node (ref "R19") (pin "1") (pinfunction "1_1") (pintype "passive"))
      (node (ref "R20") (pin "2") (pinfunction "2_2") (pintype "passive"))
      (node (ref "R21") (pin "2") (pinfunction "2_2") (pintype "passive"))
      (node (ref "R5") (pin "1") (pinfunction "1_1") (pintype "passive"))
      (node (ref "R8") (pin "2") (pinfunction "2_2") (pintype "passive"))
      (node (ref "R9") (pin "2") (pinfunction "2_2") (pintype "passive"))
      (node (ref "U1") (pin "1") (pinfunction "RUN_1") (pintype "passive"))
      (node (ref "U1") (pin "4") (pinfunction "VIN_4") (pintype "passive"))
    )
    (net (code "44") (name "unconnected-(MOD1-NC-Pad4)") (class "Default")
      (node (ref "MOD1") (pin "4") (pinfunction "NC_4") (pintype "passive+no_connect"))
    )
    (net (code "45") (name "unconnected-(MOD1-NC-Pad7)") (class "Default")
      (node (ref "MOD1") (pin "7") (pinfunction "NC_7") (pintype "passive+no_connect"))
    )
    (net (code "46") (name "unconnected-(MOD1-NC-Pad9)") (class "Default")
      (node (ref "MOD1") (pin "9") (pinfunction "NC_9") (pintype "passive+no_connect"))
    )
    (net (code "47") (name "unconnected-(MOD1-NC-Pad10)") (class "Default")
      (node (ref "MOD1") (pin "10") (pinfunction "NC_10") (pintype "passive+no_connect"))
    )
    (net (code "48") (name "unconnected-(MOD1-NC-Pad15)") (class "Default")
      (node (ref "MOD1") (pin "15") (pinfunction "NC_15") (pintype "passive+no_connect"))
    )
    (net (code "49") (name "unconnected-(MOD1-NC-Pad17)") (class "Default")
      (node (ref "MOD1") (pin "17") (pinfunction "NC_17") (pintype "passive+no_connect"))
    )
    (net (code "50") (name "unconnected-(MOD1-NC-Pad24)") (class "Default")
      (node (ref "MOD1") (pin "24") (pinfunction "NC_24") (pintype "passive+no_connect"))
    )
    (net (code "51") (name "unconnected-(MOD1-NC-Pad25)") (class "Default")
      (node (ref "MOD1") (pin "25") (pinfunction "NC_25") (pintype "passive+no_connect"))
    )
    (net (code "52") (name "unconnected-(MOD1-NC-Pad28)") (class "Default")
      (node (ref "MOD1") (pin "28") (pinfunction "NC_28") (pintype "passive+no_connect"))
    )
    (net (code "53") (name "unconnected-(MOD1-NC-Pad29)") (class "Default")
      (node (ref "MOD1") (pin "29") (pinfunction "NC_29") (pintype "passive+no_connect"))
    )
    (net (code "54") (name "unconnected-(MOD1-NC-Pad32)") (class "Default")
      (node (ref "MOD1") (pin "32") (pinfunction "NC_32") (pintype "passive+no_connect"))
    )
    (net (code "55") (name "unconnected-(MOD1-NC-Pad33)") (class "Default")
      (node (ref "MOD1") (pin "33") (pinfunction "NC_33") (pintype "passive+no_connect"))
    )
    (net (code "56") (name "unconnected-(MOD1-NC-Pad34)") (class "Default")
      (node (ref "MOD1") (pin "34") (pinfunction "NC_34") (pintype "passive+no_connect"))
    )
    (net (code "57") (name "unconnected-(MOD1-NC-Pad35)") (class "Default")
      (node (ref "MOD1") (pin "35") (pinfunction "NC_35") (pintype "passive+no_connect"))
    )
    (net (code "58") (name "unconnected-(U3-AUX_CL-Pad7)") (class "Default")
      (node (ref "U3") (pin "7") (pinfunction "AUX_CL_7") (pintype "passive+no_connect"))
    )
    (net (code "59") (name "unconnected-(U3-AUX_DA-Pad6)") (class "Default")
      (node (ref "U3") (pin "6") (pinfunction "AUX_DA_6") (pintype "passive+no_connect"))
    )
    (net (code "60") (name "unconnected-(U3-INT-Pad12)") (class "Default")
      (node (ref "U3") (pin "12") (pinfunction "INT_12") (pintype "passive+no_connect"))
    )
    (net (code "61") (name "unconnected-(U3-NC-Pad2)") (class "Default")
      (node (ref "U3") (pin "2") (pinfunction "NC_2") (pintype "passive+no_connect"))
    )
    (net (code "62") (name "unconnected-(U3-NC-Pad3)") (class "Default")
      (node (ref "U3") (pin "3") (pinfunction "NC_3") (pintype "passive+no_connect"))
    )
    (net (code "63") (name "unconnected-(U3-NC-Pad4)") (class "Default")
      (node (ref "U3") (pin "4") (pinfunction "NC_4") (pintype "passive+no_connect"))
    )
    (net (code "64") (name "unconnected-(U3-NC-Pad5)") (class "Default")
      (node (ref "U3") (pin "5") (pinfunction "NC_5") (pintype "passive+no_connect"))
    )
    (net (code "65") (name "unconnected-(U3-NC-Pad14)") (class "Default")
      (node (ref "U3") (pin "14") (pinfunction "NC_14") (pintype "passive+no_connect"))
    )
    (net (code "66") (name "unconnected-(U3-NC-Pad15)") (class "Default")
      (node (ref "U3") (pin "15") (pinfunction "NC_15") (pintype "passive+no_connect"))
    )
    (net (code "67") (name "unconnected-(U3-NC-Pad16)") (class "Default")
      (node (ref "U3") (pin "16") (pinfunction "NC_16") (pintype "passive+no_connect"))
    )
    (net (code "68") (name "unconnected-(U3-NC-Pad17)") (class "Default")
      (node (ref "U3") (pin "17") (pinfunction "NC_17") (pintype "passive+no_connect"))
    )
    (net (code "69") (name "unconnected-(U3-RESV-Pad19)") (class "Default")
      (node (ref "U3") (pin "19") (pinfunction "RESV_19") (pintype "passive+no_connect"))
    )
    (net (code "70") (name "unconnected-(U3-RESV-Pad21)") (class "Default")
      (node (ref "U3") (pin "21") (pinfunction "RESV_21") (pintype "passive+no_connect"))
    )
    (net (code "71") (name "unconnected-(U3-RESV-Pad22)") (class "Default")
      (node (ref "U3") (pin "22") (pinfunction "RESV_22") (pintype "passive+no_connect"))
    )
    (net (code "72") (name "unconnected-(U6-CSB-Pad8)") (class "Default")
      (node (ref "U6") (pin "8") (pinfunction "CSB_8") (pintype "passive"))
    )
    (net (code "73") (name "unconnected-(U6-INT0-Pad7)") (class "Default")
      (node (ref "U6") (pin "7") (pinfunction "INT0_7") (pintype "passive+no_connect"))
    )
    (net (code "74") (name "unconnected-(U6-INT1-Pad1)") (class "Default")
      (node (ref "U6") (pin "1") (pinfunction "INT1_1") (pintype "passive+no_connect"))
    )
    (net (code "75") (name "unconnected-(U6-NC-Pad4)") (class "Default")
      (node (ref "U6") (pin "4") (pinfunction "NC_4") (pintype "passive+no_connect"))
    )
    (net (code "76") (name "unconnected-(USB1-SBU1-PadA8)") (class "Default")
      (node (ref "USB1") (pin "A8") (pinfunction "SBU1_A8") (pintype "passive+no_connect"))
    )
    (net (code "77") (name "unconnected-(USB1-SBU2-PadB8)") (class "Default")
      (node (ref "USB1") (pin "B8") (pinfunction "SBU2_B8") (pintype "passive+no_connect"))
    )
  )
)
